# elevationsrotor-prinzip.net
KiCad netlist of a schematic drawn in EAGLE
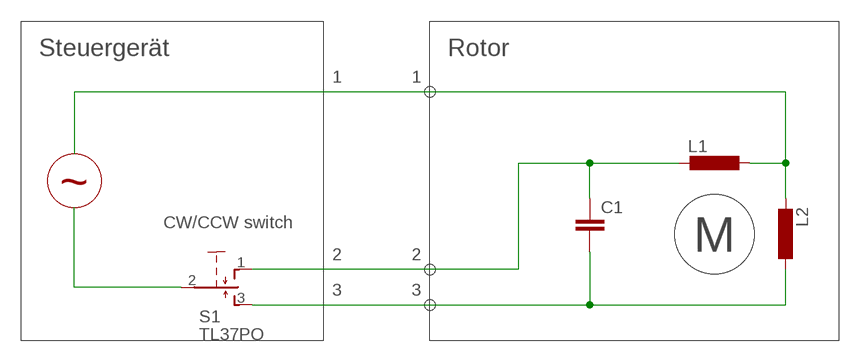
[diagram p0: schematic, sheet 1]

(export (version "E")
  (design (tool "Eeschema 10.0.6"))
  (components
    (comp (ref "C1")
      (value "C-EU025-040X050")
      (footprint "eagle-import:C025-040X050")
      (libsource (lib "eagle-import") (part "C-EU025-040X050"))
    )
    (comp (ref "L1")
      (value "L-EUL1812")
      (footprint "eagle-import:L1812")
      (libsource (lib "eagle-import") (part "L-EUL1812"))
    )
    (comp (ref "L2")
      (value "L-EUL1812")
      (footprint "eagle-import:L1812")
      (libsource (lib "eagle-import") (part "L-EUL1812"))
    )
    (comp (ref "S1")
      (value "TL37PO")
      (footprint "eagle-import:TL3XPO")
      (libsource (lib "eagle-import") (part "TL37PO"))
    )
  )
  (nets
    (net (code "1") (name "Net-(L1-Pad1)") (class "Default")
      (node (ref "L1") (pin "1") (pinfunction "1_1") (pintype "passive"))
      (node (ref "L2") (pin "2") (pinfunction "2_2") (pintype "passive"))
    )
    (net (code "2") (name "Net-(S1-O)") (class "Default")
      (node (ref "C1") (pin "1") (pinfunction "1_1") (pintype "passive"))
      (node (ref "L1") (pin "2") (pinfunction "2_2") (pintype "passive"))
      (node (ref "S1") (pin "1") (pinfunction "O_1") (pintype "passive"))
    )
    (net (code "3") (name "Net-(S1-S)") (class "Default")
      (node (ref "C1") (pin "2") (pinfunction "2_2") (pintype "passive"))
      (node (ref "L2") (pin "1") (pinfunction "1_1") (pintype "passive"))
      (node (ref "S1") (pin "3") (pinfunction "S_3") (pintype "passive"))
    )
    (net (code "4") (name "unconnected-(S1-P-Pad2)") (class "Default")
      (node (ref "S1") (pin "2") (pinfunction "P_2") (pintype "passive"))
    )
  )
)
